# SenseoControl.net
KiCad netlist of a schematic drawn in EAGLE
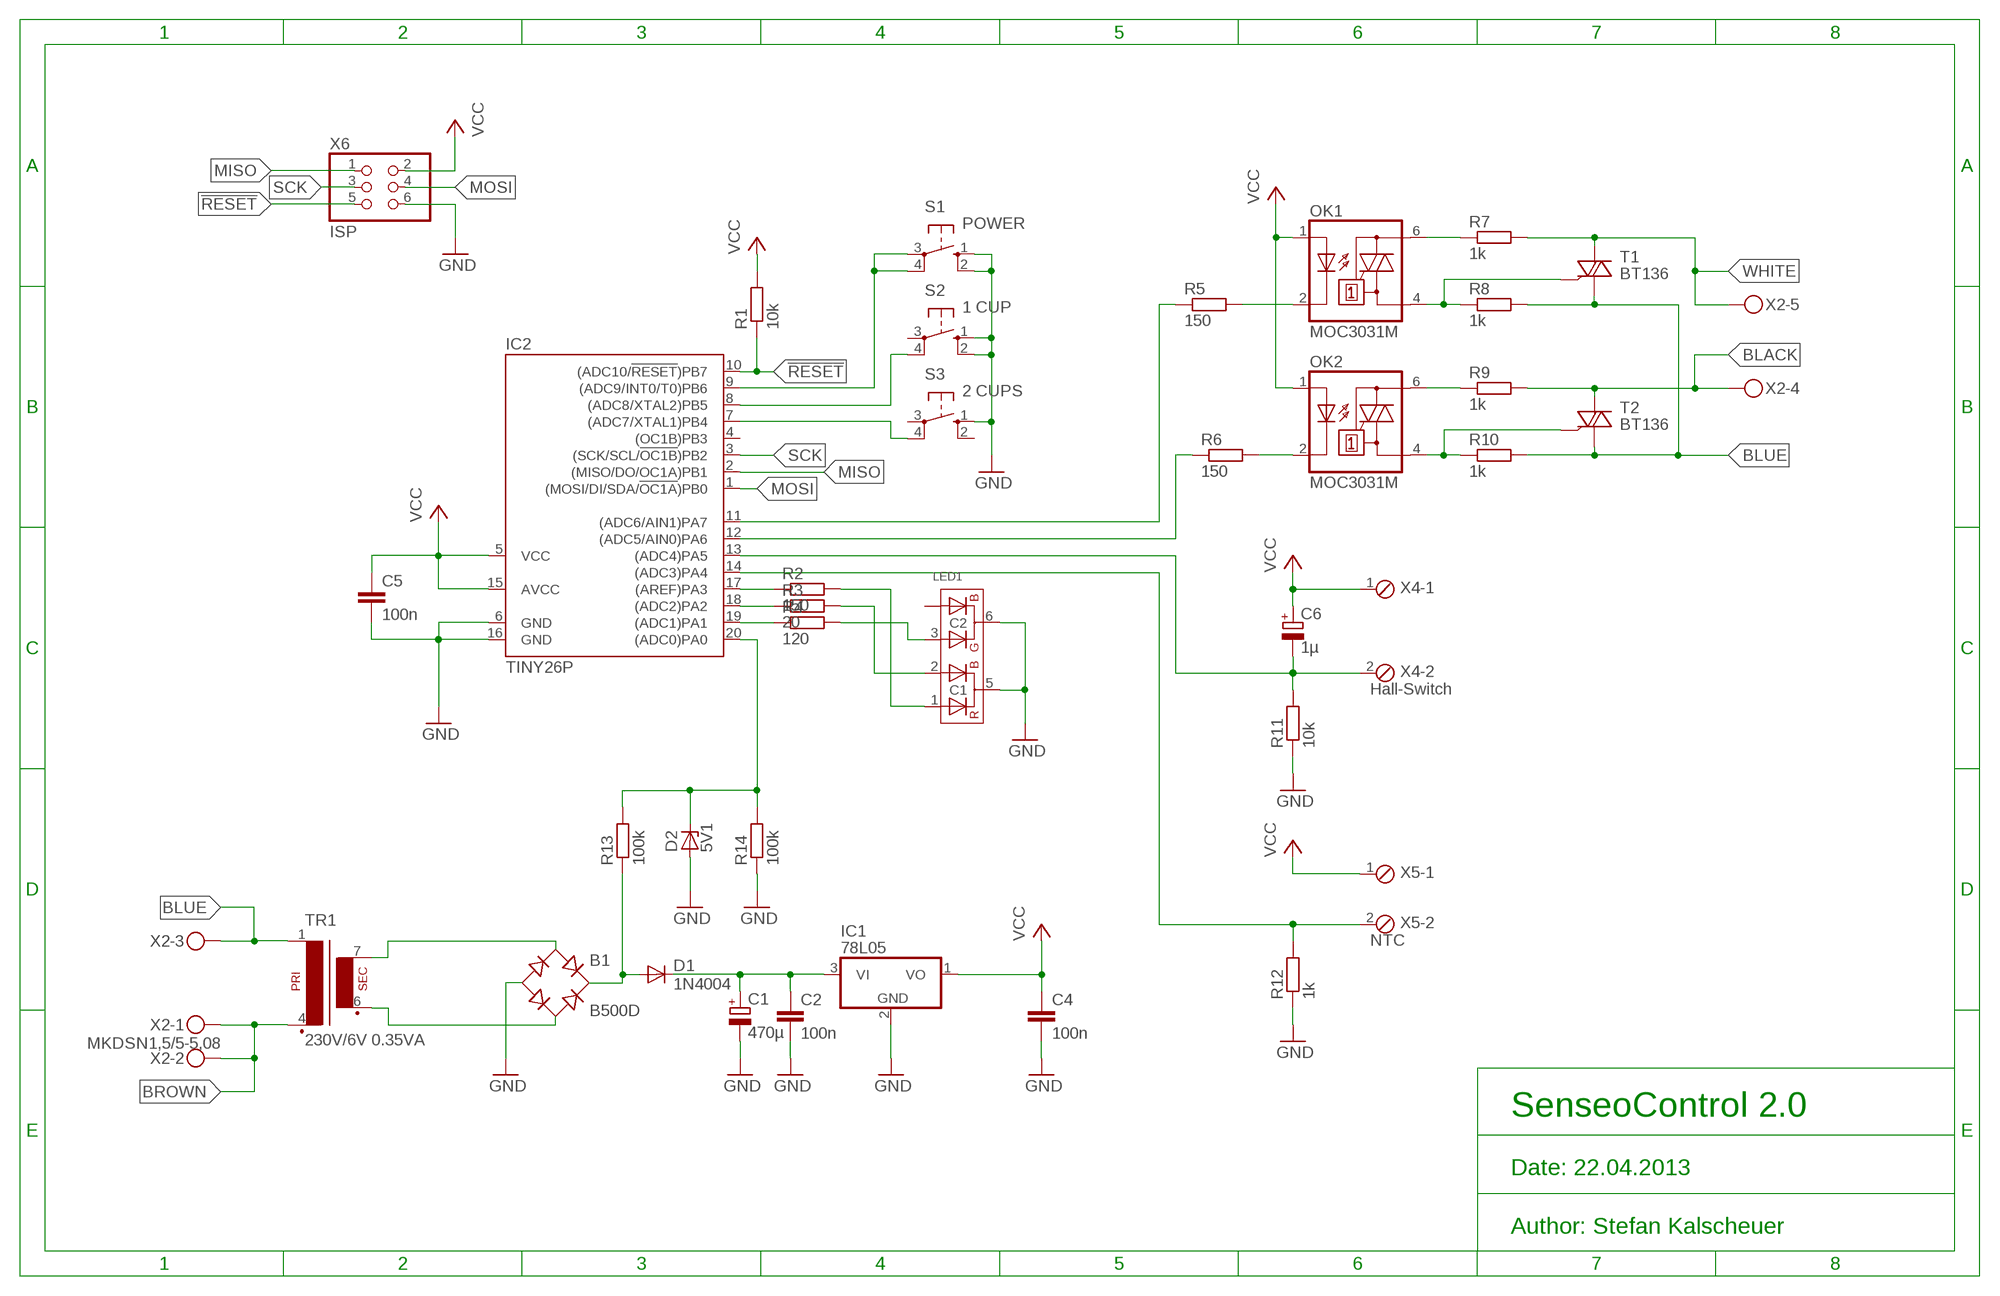
[diagram p0: schematic, sheet 1]

(export (version "E")
  (design (tool "Eeschema 10.0.6"))
  (components
    (comp (ref "B1")
      (value "B500D")
      (footprint "eagle-import:B-DIL")
      (libsource (lib "eagle-import") (part "B-DIL"))
    )
    (comp (ref "C1")
      (value "470µ")
      (footprint "eagle-import:E2,5-6")
      (libsource (lib "eagle-import") (part "CPOL-EUE2.5-6"))
    )
    (comp (ref "C2")
      (value "100n")
      (footprint "eagle-import:C025-024X044")
      (libsource (lib "eagle-import") (part "C-EU025-024X044"))
    )
    (comp (ref "C4")
      (value "100n")
      (footprint "eagle-import:C025-024X044")
      (libsource (lib "eagle-import") (part "C-EU025-024X044"))
    )
    (comp (ref "C5")
      (value "100n")
      (footprint "eagle-import:C025-024X044")
      (libsource (lib "eagle-import") (part "C-EU025-024X044"))
    )
    (comp (ref "C6")
      (value "1µ")
      (footprint "eagle-import:TT2D5")
      (libsource (lib "eagle-import") (part "CPOL-EUTT2D5"))
    )
    (comp (ref "D1")
      (value "1N4004")
      (footprint "eagle-import:D-2.5")
      (libsource (lib "eagle-import") (part "DIODE-D-2.5"))
    )
    (comp (ref "D2")
      (value "5V1")
      (footprint "eagle-import:ZDIO-7.5")
      (libsource (lib "eagle-import") (part "ZENER-DIODEZD-7.5"))
    )
    (comp (ref "IC1")
      (value "78L05")
      (footprint "eagle-import:TO92-A")
      (libsource (lib "eagle-import") (part "78L2"))
    )
    (comp (ref "IC2")
      (value "TINY26P")
      (footprint "eagle-import:DIL20")
      (fields (field (name "MPN") "ATTINY261-20PU"))
      (libsource (lib "eagle-import") (part "TINY26P"))
    )
    (comp (ref "LED1")
      (value "LF5")
      (footprint "eagle-import:LF5")
      (libsource (lib "eagle-import") (part "LF5"))
    )
    (comp (ref "OK1")
      (value "MOC3031M")
      (footprint "eagle-import:DIL06")
      (fields (field (name "MF") "FAIRCHILD SEMICONDUCTOR"))
      (libsource (lib "eagle-import") (part "MOC3031M"))
    )
    (comp (ref "OK2")
      (value "MOC3031M")
      (footprint "eagle-import:DIL06")
      (fields (field (name "MF") "FAIRCHILD SEMICONDUCTOR"))
      (libsource (lib "eagle-import") (part "MOC3031M"))
    )
    (comp (ref "R1")
      (value "10k")
      (footprint "eagle-import:0207_12")
      (libsource (lib "eagle-import") (part "R-EU_0207/12"))
    )
    (comp (ref "R2")
      (value "150")
      (footprint "eagle-import:0204_7")
      (libsource (lib "eagle-import") (part "R-EU_0204/7"))
    )
    (comp (ref "R3")
      (value "20")
      (footprint "eagle-import:0204_7")
      (libsource (lib "eagle-import") (part "R-EU_0204/7"))
    )
    (comp (ref "R4")
      (value "120")
      (footprint "eagle-import:0204_7")
      (libsource (lib "eagle-import") (part "R-EU_0204/7"))
    )
    (comp (ref "R5")
      (value "150")
      (footprint "eagle-import:0204_7")
      (libsource (lib "eagle-import") (part "R-EU_0204/7"))
    )
    (comp (ref "R6")
      (value "150")
      (footprint "eagle-import:0204_7")
      (libsource (lib "eagle-import") (part "R-EU_0204/7"))
    )
    (comp (ref "R7")
      (value "1k")
      (footprint "eagle-import:0204_7")
      (libsource (lib "eagle-import") (part "R-EU_0204/7"))
    )
    (comp (ref "R8")
      (value "1k")
      (footprint "eagle-import:0204_7")
      (libsource (lib "eagle-import") (part "R-EU_0204/7"))
    )
    (comp (ref "R9")
      (value "1k")
      (footprint "eagle-import:0204_7")
      (libsource (lib "eagle-import") (part "R-EU_0204/7"))
    )
    (comp (ref "R10")
      (value "1k")
      (footprint "eagle-import:0204_7")
      (libsource (lib "eagle-import") (part "R-EU_0204/7"))
    )
    (comp (ref "R11")
      (value "10k")
      (footprint "eagle-import:0204_7")
      (libsource (lib "eagle-import") (part "R-EU_0204/7"))
    )
    (comp (ref "R12")
      (value "1k")
      (footprint "eagle-import:0204_7")
      (libsource (lib "eagle-import") (part "R-EU_0204/7"))
    )
    (comp (ref "R13")
      (value "100k")
      (footprint "eagle-import:0204_7")
      (libsource (lib "eagle-import") (part "R-EU_0204/7"))
    )
    (comp (ref "R14")
      (value "100k")
      (footprint "eagle-import:0204_7")
      (libsource (lib "eagle-import") (part "R-EU_0204/7"))
    )
    (comp (ref "S1")
      (value "POWER")
      (footprint "eagle-import:B3F-10XX-A")
      (libsource (lib "eagle-import") (part "10-XXA"))
    )
    (comp (ref "S2")
      (value "1 CUP")
      (footprint "eagle-import:B3F-10XX-A")
      (libsource (lib "eagle-import") (part "10-XXA"))
    )
    (comp (ref "S3")
      (value "2 CUPS")
      (footprint "eagle-import:B3F-10XX-A")
      (libsource (lib "eagle-import") (part "10-XXA"))
    )
    (comp (ref "T1")
      (value "BT136")
      (footprint "eagle-import:TO220AB")
      (libsource (lib "eagle-import") (part "BT136"))
    )
    (comp (ref "T2")
      (value "BT136")
      (footprint "eagle-import:TO220AB")
      (libsource (lib "eagle-import") (part "BT136"))
    )
    (comp (ref "TR1")
      (value "230V/6V 0.35VA")
      (footprint "eagle-import:EE20-1")
      (libsource (lib "eagle-import") (part "EE20-1"))
    )
    (comp (ref "X2")
      (value "MKDSN1,5/5-5,08")
      (footprint "eagle-import:MKDSN1,5_5-5,08")
      (fields (field (name "MPN") "SMKDSN1,5/5-5,08"))
      (libsource (lib "eagle-import") (part "MKDSN1,5/5-5,08"))
    )
    (comp (ref "X4")
      (value "Hall-Switch")
      (footprint "eagle-import:2POL254")
      (libsource (lib "eagle-import") (part "MPT2"))
    )
    (comp (ref "X5")
      (value "NTC")
      (footprint "eagle-import:2POL254")
      (libsource (lib "eagle-import") (part "MPT2"))
    )
    (comp (ref "X6")
      (value "ISP")
      (footprint "eagle-import:2X03")
      (libsource (lib "eagle-import") (part "PINHD-2X3"))
    )
  )
  (nets
    (net (code "1") (name "/~{RESET}") (class "Default")
      (node (ref "IC2") (pin "10") (pinfunction "(ADC10/~{RESET})PB7_10") (pintype "bidirectional"))
      (node (ref "R1") (pin "1") (pinfunction "1_1") (pintype "passive"))
      (node (ref "X6") (pin "5") (pinfunction "5_5") (pintype "passive"))
    )
    (net (code "2") (name "BLACK") (class "Default")
      (node (ref "R9") (pin "2") (pinfunction "2_2") (pintype "passive"))
      (node (ref "T2") (pin "2") (pinfunction "A2_2") (pintype "passive"))
      (node (ref "X2") (pin "4") (pinfunction "KL_4") (pintype "passive"))
    )
    (net (code "3") (name "BLUE") (class "Default")
      (node (ref "R10") (pin "2") (pinfunction "2_2") (pintype "passive"))
      (node (ref "R8") (pin "2") (pinfunction "2_2") (pintype "passive"))
      (node (ref "T1") (pin "1") (pinfunction "A1_1") (pintype "passive"))
      (node (ref "T2") (pin "1") (pinfunction "A1_1") (pintype "passive"))
      (node (ref "TR1") (pin "1") (pinfunction "P1_1") (pintype "passive"))
      (node (ref "X2") (pin "3") (pinfunction "KL_3") (pintype "passive"))
    )
    (net (code "4") (name "BROWN") (class "Default")
      (node (ref "TR1") (pin "4") (pinfunction "P2_4") (pintype "passive"))
      (node (ref "X2") (pin "1") (pinfunction "KL_1") (pintype "passive"))
      (node (ref "X2") (pin "2") (pinfunction "KL_2") (pintype "passive"))
    )
    (net (code "5") (name "GND") (class "Default")
      (node (ref "B1") (pin "-") (pinfunction "-_-") (pintype "passive"))
      (node (ref "C1") (pin "-") (pinfunction "-_-") (pintype "passive"))
      (node (ref "C2") (pin "2") (pinfunction "2_2") (pintype "passive"))
      (node (ref "C4") (pin "2") (pinfunction "2_2") (pintype "passive"))
      (node (ref "C5") (pin "2") (pinfunction "2_2") (pintype "passive"))
      (node (ref "D2") (pin "A") (pinfunction "A_A") (pintype "passive"))
      (node (ref "IC1") (pin "2") (pinfunction "GND_2") (pintype "passive"))
      (node (ref "IC2") (pin "16") (pinfunction "GND_16") (pintype "power_in"))
      (node (ref "IC2") (pin "6") (pinfunction "GND_6") (pintype "power_in"))
      (node (ref "LED1") (pin "5") (pinfunction "C1_5") (pintype "bidirectional"))
      (node (ref "LED1") (pin "6") (pinfunction "C2_6") (pintype "bidirectional"))
      (node (ref "R11") (pin "1") (pinfunction "1_1") (pintype "passive"))
      (node (ref "R12") (pin "1") (pinfunction "1_1") (pintype "passive"))
      (node (ref "R14") (pin "1") (pinfunction "1_1") (pintype "passive"))
      (node (ref "S1") (pin "1") (pinfunction "S_1") (pintype "passive"))
      (node (ref "S1") (pin "2") (pinfunction "S1_2") (pintype "passive"))
      (node (ref "S2") (pin "1") (pinfunction "S_1") (pintype "passive"))
      (node (ref "S2") (pin "2") (pinfunction "S1_2") (pintype "passive"))
      (node (ref "S3") (pin "1") (pinfunction "S_1") (pintype "passive"))
      (node (ref "X6") (pin "6") (pinfunction "6_6") (pintype "passive"))
    )
    (net (code "6") (name "MISO") (class "Default")
      (node (ref "IC2") (pin "2") (pinfunction "(MISO/DO/OC1A)PB1_2") (pintype "bidirectional"))
      (node (ref "X6") (pin "1") (pinfunction "1_1") (pintype "passive"))
    )
    (net (code "7") (name "MOSI") (class "Default")
      (node (ref "IC2") (pin "1") (pinfunction "(MOSI/DI/SDA/~{OC1A})PB0_1") (pintype "bidirectional"))
      (node (ref "X6") (pin "4") (pinfunction "4_4") (pintype "passive"))
    )
    (net (code "8") (name "Net-(B1-Pad+)") (class "Default")
      (node (ref "B1") (pin "+") (pinfunction "+_+") (pintype "passive"))
      (node (ref "D1") (pin "A") (pinfunction "A_A") (pintype "passive"))
      (node (ref "R13") (pin "1") (pinfunction "1_1") (pintype "passive"))
    )
    (net (code "9") (name "Net-(IC1-VI)") (class "Default")
      (node (ref "C1") (pin "+") (pinfunction "+_+") (pintype "passive"))
      (node (ref "C2") (pin "1") (pinfunction "1_1") (pintype "passive"))
      (node (ref "D1") (pin "C") (pinfunction "C_C") (pintype "passive"))
      (node (ref "IC1") (pin "3") (pinfunction "VI_3") (pintype "input"))
    )
    (net (code "10") (name "Net-(IC2-(ADC0)PA0)") (class "Default")
      (node (ref "D2") (pin "C") (pinfunction "C_C") (pintype "passive"))
      (node (ref "IC2") (pin "20") (pinfunction "(ADC0)PA0_20") (pintype "bidirectional"))
      (node (ref "R13") (pin "2") (pinfunction "2_2") (pintype "passive"))
      (node (ref "R14") (pin "2") (pinfunction "2_2") (pintype "passive"))
    )
    (net (code "11") (name "Net-(IC2-(ADC1)PA1)") (class "Default")
      (node (ref "IC2") (pin "19") (pinfunction "(ADC1)PA1_19") (pintype "bidirectional"))
      (node (ref "R4") (pin "1") (pinfunction "1_1") (pintype "passive"))
    )
    (net (code "12") (name "Net-(IC2-(ADC2)PA2)") (class "Default")
      (node (ref "IC2") (pin "18") (pinfunction "(ADC2)PA2_18") (pintype "bidirectional"))
      (node (ref "R3") (pin "1") (pinfunction "1_1") (pintype "passive"))
    )
    (net (code "13") (name "Net-(IC2-(ADC3)PA4)") (class "Default")
      (node (ref "IC2") (pin "14") (pinfunction "(ADC3)PA4_14") (pintype "bidirectional"))
      (node (ref "R12") (pin "2") (pinfunction "2_2") (pintype "passive"))
      (node (ref "X5") (pin "2") (pinfunction "1_2") (pintype "passive"))
    )
    (net (code "14") (name "Net-(IC2-(ADC4)PA5)") (class "Default")
      (node (ref "C6") (pin "-") (pinfunction "-_-") (pintype "passive"))
      (node (ref "IC2") (pin "13") (pinfunction "(ADC4)PA5_13") (pintype "bidirectional"))
      (node (ref "R11") (pin "2") (pinfunction "2_2") (pintype "passive"))
      (node (ref "X4") (pin "2") (pinfunction "1_2") (pintype "passive"))
    )
    (net (code "15") (name "Net-(IC2-(ADC5{slash}AIN0)PA6)") (class "Default")
      (node (ref "IC2") (pin "12") (pinfunction "(ADC5/AIN0)PA6_12") (pintype "bidirectional"))
      (node (ref "R6") (pin "1") (pinfunction "1_1") (pintype "passive"))
    )
    (net (code "16") (name "Net-(IC2-(ADC6{slash}AIN1)PA7)") (class "Default")
      (node (ref "IC2") (pin "11") (pinfunction "(ADC6/AIN1)PA7_11") (pintype "bidirectional"))
      (node (ref "R5") (pin "1") (pinfunction "1_1") (pintype "passive"))
    )
    (net (code "17") (name "Net-(IC2-(ADC7{slash}XTAL1)PB4)") (class "Default")
      (node (ref "IC2") (pin "7") (pinfunction "(ADC7/XTAL1)PB4_7") (pintype "bidirectional"))
      (node (ref "S3") (pin "4") (pinfunction "P1_4") (pintype "passive"))
    )
    (net (code "18") (name "Net-(IC2-(ADC8{slash}XTAL2)PB5)") (class "Default")
      (node (ref "IC2") (pin "8") (pinfunction "(ADC8/XTAL2)PB5_8") (pintype "bidirectional"))
      (node (ref "S2") (pin "4") (pinfunction "P1_4") (pintype "passive"))
    )
    (net (code "19") (name "Net-(IC2-(ADC9{slash}INT0{slash}T0)PB6)") (class "Default")
      (node (ref "IC2") (pin "9") (pinfunction "(ADC9/INT0/T0)PB6_9") (pintype "bidirectional"))
      (node (ref "S1") (pin "3") (pinfunction "P_3") (pintype "passive"))
      (node (ref "S1") (pin "4") (pinfunction "P1_4") (pintype "passive"))
    )
    (net (code "20") (name "Net-(IC2-(AREF)PA3)") (class "Default")
      (node (ref "IC2") (pin "17") (pinfunction "(AREF)PA3_17") (pintype "bidirectional"))
      (node (ref "R2") (pin "1") (pinfunction "1_1") (pintype "passive"))
    )
    (net (code "21") (name "Net-(LED1-A-BLUE)") (class "Default")
      (node (ref "LED1") (pin "2") (pinfunction "A-BLUE_2") (pintype "bidirectional"))
      (node (ref "R3") (pin "2") (pinfunction "2_2") (pintype "passive"))
    )
    (net (code "22") (name "Net-(LED1-A-RED)") (class "Default")
      (node (ref "LED1") (pin "1") (pinfunction "A-RED_1") (pintype "bidirectional"))
      (node (ref "R2") (pin "2") (pinfunction "2_2") (pintype "passive"))
    )
    (net (code "23") (name "Net-(LED1-A_GREEN)") (class "Default")
      (node (ref "LED1") (pin "3") (pinfunction "A_GREEN_3") (pintype "bidirectional"))
      (node (ref "R4") (pin "2") (pinfunction "2_2") (pintype "passive"))
    )
    (net (code "24") (name "Net-(OK1-A1)") (class "Default")
      (node (ref "OK1") (pin "4") (pinfunction "A1_4") (pintype "passive"))
      (node (ref "R8") (pin "1") (pinfunction "1_1") (pintype "passive"))
      (node (ref "T1") (pin "3") (pinfunction "G_3") (pintype "passive"))
    )
    (net (code "25") (name "Net-(OK1-A2)") (class "Default")
      (node (ref "OK1") (pin "6") (pinfunction "A2_6") (pintype "passive"))
      (node (ref "R7") (pin "1") (pinfunction "1_1") (pintype "passive"))
    )
    (net (code "26") (name "Net-(OK1-C)") (class "Default")
      (node (ref "OK1") (pin "2") (pinfunction "C_2") (pintype "passive"))
      (node (ref "R5") (pin "2") (pinfunction "2_2") (pintype "passive"))
    )
    (net (code "27") (name "Net-(OK2-A1)") (class "Default")
      (node (ref "OK2") (pin "4") (pinfunction "A1_4") (pintype "passive"))
      (node (ref "R10") (pin "1") (pinfunction "1_1") (pintype "passive"))
      (node (ref "T2") (pin "3") (pinfunction "G_3") (pintype "passive"))
    )
    (net (code "28") (name "Net-(OK2-A2)") (class "Default")
      (node (ref "OK2") (pin "6") (pinfunction "A2_6") (pintype "passive"))
      (node (ref "R9") (pin "1") (pinfunction "1_1") (pintype "passive"))
    )
    (net (code "29") (name "Net-(OK2-C)") (class "Default")
      (node (ref "OK2") (pin "2") (pinfunction "C_2") (pintype "passive"))
      (node (ref "R6") (pin "2") (pinfunction "2_2") (pintype "passive"))
    )
    (net (code "30") (name "Net-(TR1-S3)") (class "Default")
      (node (ref "B1") (pin "AC2") (pinfunction "AC2_AC2") (pintype "passive"))
      (node (ref "TR1") (pin "6") (pinfunction "S3_6") (pintype "passive"))
    )
    (net (code "31") (name "Net-(TR1-S4)") (class "Default")
      (node (ref "B1") (pin "AC1") (pinfunction "AC1_AC1") (pintype "passive"))
      (node (ref "TR1") (pin "7") (pinfunction "S4_7") (pintype "passive"))
    )
    (net (code "32") (name "SCK") (class "Default")
      (node (ref "IC2") (pin "3") (pinfunction "(SCK/SCL/~{OC1B})PB2_3") (pintype "bidirectional"))
      (node (ref "X6") (pin "3") (pinfunction "3_3") (pintype "passive"))
    )
    (net (code "33") (name "VCC") (class "Default")
      (node (ref "C4") (pin "1") (pinfunction "1_1") (pintype "passive"))
      (node (ref "C5") (pin "1") (pinfunction "1_1") (pintype "passive"))
      (node (ref "C6") (pin "+") (pinfunction "+_+") (pintype "passive"))
      (node (ref "IC1") (pin "1") (pinfunction "VO_1") (pintype "passive"))
      (node (ref "IC2") (pin "15") (pinfunction "AVCC_15") (pintype "power_in"))
      (node (ref "IC2") (pin "5") (pinfunction "VCC_5") (pintype "power_in"))
      (node (ref "OK1") (pin "1") (pinfunction "A_1") (pintype "passive"))
      (node (ref "OK2") (pin "1") (pinfunction "A_1") (pintype "passive"))
      (node (ref "R1") (pin "2") (pinfunction "2_2") (pintype "passive"))
      (node (ref "X4") (pin "1") (pinfunction "1_1") (pintype "passive"))
      (node (ref "X5") (pin "1") (pinfunction "1_1") (pintype "passive"))
      (node (ref "X6") (pin "2") (pinfunction "2_2") (pintype "passive"))
    )
    (net (code "34") (name "WHITE") (class "Default")
      (node (ref "R7") (pin "2") (pinfunction "2_2") (pintype "passive"))
      (node (ref "T1") (pin "2") (pinfunction "A2_2") (pintype "passive"))
      (node (ref "X2") (pin "5") (pinfunction "KL_5") (pintype "passive"))
    )
    (net (code "35") (name "unconnected-(IC2-(OC1B)PB3-Pad4)") (class "Default")
      (node (ref "IC2") (pin "4") (pinfunction "(OC1B)PB3_4") (pintype "bidirectional"))
    )
    (net (code "36") (name "unconnected-(LED1-A-BLUE2-Pad4)") (class "Default")
      (node (ref "LED1") (pin "4") (pinfunction "A-BLUE2_4") (pintype "bidirectional"))
    )
    (net (code "37") (name "unconnected-(S2-P-Pad3)") (class "Default")
      (node (ref "S2") (pin "3") (pinfunction "P_3") (pintype "passive"))
    )
    (net (code "38") (name "unconnected-(S3-P-Pad3)") (class "Default")
      (node (ref "S3") (pin "3") (pinfunction "P_3") (pintype "passive"))
    )
    (net (code "39") (name "unconnected-(S3-S1-Pad2)") (class "Default")
      (node (ref "S3") (pin "2") (pinfunction "S1_2") (pintype "passive"))
    )
  )
)
